# cm3-adaptor-board.net
KiCad netlist of a schematic drawn in EAGLE
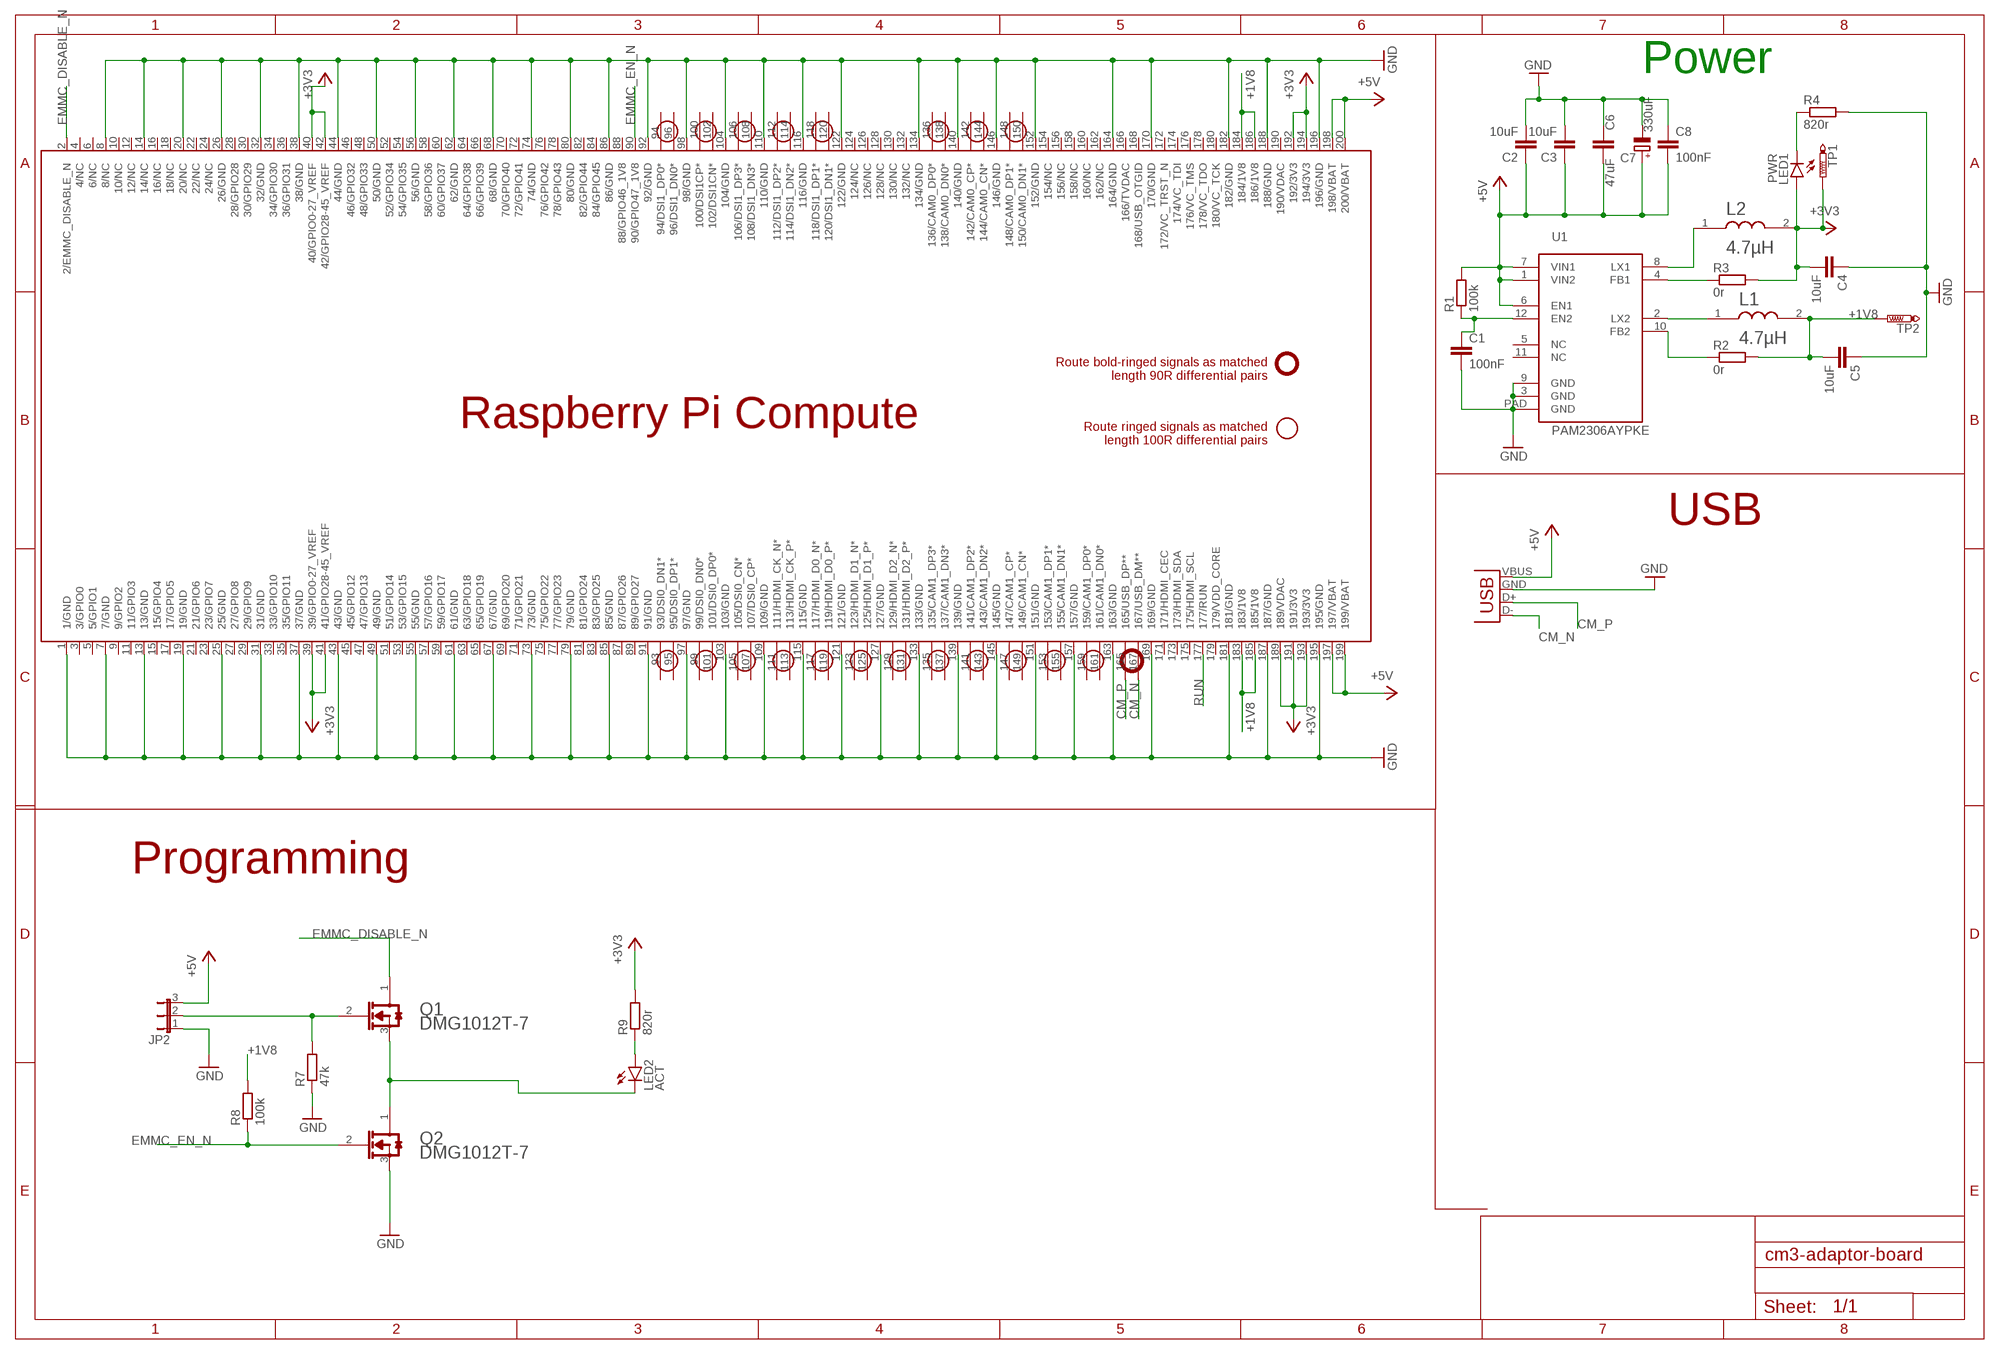
[diagram p0: schematic, sheet 1]

(export (version "E")
  (design (tool "Eeschema 10.0.6"))
  (components
    (comp (ref "C1")
      (value "100nF")
      (footprint "eagle-import:C0603")
      (libsource (lib "eagle-import") (part "C-EUC0603"))
    )
    (comp (ref "C2")
      (value "10uF")
      (footprint "eagle-import:C0805")
      (libsource (lib "eagle-import") (part "C-EUC0805"))
    )
    (comp (ref "C3")
      (value "10uF")
      (footprint "eagle-import:C0805")
      (libsource (lib "eagle-import") (part "C-EUC0805"))
    )
    (comp (ref "C4")
      (value "10uF")
      (footprint "eagle-import:C0805")
      (libsource (lib "eagle-import") (part "C-EUC0805"))
    )
    (comp (ref "C5")
      (value "10uF")
      (footprint "eagle-import:C0805")
      (libsource (lib "eagle-import") (part "C-EUC0805"))
    )
    (comp (ref "C6")
      (value "47uF")
      (footprint "eagle-import:C1206")
      (libsource (lib "eagle-import") (part "C-EUC1206"))
    )
    (comp (ref "C7")
      (value "330uF")
      (footprint "eagle-import:PANASONIC_D")
      (libsource (lib "eagle-import") (part "CPOL-EUD"))
    )
    (comp (ref "C8")
      (value "100nF")
      (footprint "eagle-import:C0603")
      (libsource (lib "eagle-import") (part "C-EUC0603"))
    )
    (comp (ref "JP1")
      (value "USB-A-H")
      (footprint "eagle-import:USB-A-H")
      (libsource (lib "eagle-import") (part "USB-A-H"))
    )
    (comp (ref "JP2")
      (value "JP2E")
      (footprint "eagle-import:JP2")
      (libsource (lib "eagle-import") (part "JP2E"))
    )
    (comp (ref "L1")
      (value "BOURNS_SRN4018-4R7MBOURNS_SRN4018-4R7M_0_0")
      (footprint "eagle-import:BOURNS_SRN4018-4R7M_0")
      (fields
        (field (name "DIGIKEY_PART_NUMBER") "SRN4018-4R7MCT-ND")
        (field (name "MF") "Bourns")
        (field (name "MOUSER_PART_NUMBER") "652-SRN4018-4R7M")
      )
      (libsource (lib "eagle-import") (part "BOURNS_SRN4018-4R7MBOURNS_SRN4018-4R7M_0_0"))
    )
    (comp (ref "L2")
      (value "BOURNS_SRN4018-4R7MBOURNS_SRN4018-4R7M_0_0")
      (footprint "eagle-import:BOURNS_SRN4018-4R7M_0")
      (fields
        (field (name "DIGIKEY_PART_NUMBER") "SRN4018-4R7MCT-ND")
        (field (name "MF") "Bourns")
        (field (name "MOUSER_PART_NUMBER") "652-SRN4018-4R7M")
      )
      (libsource (lib "eagle-import") (part "BOURNS_SRN4018-4R7MBOURNS_SRN4018-4R7M_0_0"))
    )
    (comp (ref "LED1")
      (value "PWR")
      (footprint "eagle-import:CHIP-LED0603")
      (libsource (lib "eagle-import") (part "LEDCHIP-LED0603"))
    )
    (comp (ref "LED2")
      (value "ACT")
      (footprint "eagle-import:CHIP-LED0603")
      (libsource (lib "eagle-import") (part "LEDCHIP-LED0603"))
    )
    (comp (ref "PCB1")
      (value "RPI_COMPUTE")
      (footprint "eagle-import:RPI_COMPUTE")
      (libsource (lib "eagle-import") (part "RPI_COMPUTE"))
    )
    (comp (ref "Q1")
      (value "DIODES_DMG1012T-7DIODES_DMG1012T-7_0_0")
      (footprint "eagle-import:DIODES_DMG1012T-7_0")
      (fields
        (field (name "DIGIKEY_PART_NUMBER") "DMG1012T-7DICT-ND")
        (field (name "MF") "Diodes")
        (field (name "MOUSER_PART_NUMBER") "621-DMG1012T-7")
      )
      (libsource (lib "eagle-import") (part "DIODES_DMG1012T-7DIODES_DMG1012T-7_0_0"))
    )
    (comp (ref "Q2")
      (value "DIODES_DMG1012T-7DIODES_DMG1012T-7_0_0")
      (footprint "eagle-import:DIODES_DMG1012T-7_0")
      (fields
        (field (name "DIGIKEY_PART_NUMBER") "DMG1012T-7DICT-ND")
        (field (name "MF") "Diodes")
        (field (name "MOUSER_PART_NUMBER") "621-DMG1012T-7")
      )
      (libsource (lib "eagle-import") (part "DIODES_DMG1012T-7DIODES_DMG1012T-7_0_0"))
    )
    (comp (ref "R1")
      (value "100k")
      (footprint "eagle-import:R0603")
      (libsource (lib "eagle-import") (part "R-EU_R0603"))
    )
    (comp (ref "R2")
      (value "0r")
      (footprint "eagle-import:R0603")
      (libsource (lib "eagle-import") (part "R-EU_R0603"))
    )
    (comp (ref "R3")
      (value "0r")
      (footprint "eagle-import:R0603")
      (libsource (lib "eagle-import") (part "R-EU_R0603"))
    )
    (comp (ref "R4")
      (value "820r")
      (footprint "eagle-import:R0603")
      (libsource (lib "eagle-import") (part "R-EU_R0603"))
    )
    (comp (ref "R7")
      (value "47k")
      (footprint "eagle-import:R0603")
      (libsource (lib "eagle-import") (part "R-EU_R0603"))
    )
    (comp (ref "R8")
      (value "100k")
      (footprint "eagle-import:R0603")
      (libsource (lib "eagle-import") (part "R-EU_R0603"))
    )
    (comp (ref "R9")
      (value "820r")
      (footprint "eagle-import:R0603")
      (libsource (lib "eagle-import") (part "R-EU_R0603"))
    )
    (comp (ref "TP1")
      (value "PTR1B1,27")
      (footprint "eagle-import:B1,27")
      (libsource (lib "eagle-import") (part "PTR1B1,27"))
    )
    (comp (ref "TP2")
      (value "PTR1B1,27")
      (footprint "eagle-import:B1,27")
      (libsource (lib "eagle-import") (part "PTR1B1,27"))
    )
    (comp (ref "U1")
      (value "PAM2306AYPKE")
      (footprint "eagle-import:WDFN-12L")
      (libsource (lib "eagle-import") (part "PAM2306AYPKE"))
    )
  )
  (nets
    (net (code "1") (name "+3V3") (class "Default")
      (node (ref "C4") (pin "2") (pinfunction "2_2") (pintype "passive"))
      (node (ref "L2") (pin "2") (pinfunction "2_2") (pintype "bidirectional"))
      (node (ref "LED1") (pin "A") (pinfunction "A_A") (pintype "passive"))
      (node (ref "PCB1") (pin "189") (pinfunction "189/VDAC_189") (pintype "bidirectional"))
      (node (ref "PCB1") (pin "191") (pinfunction "191/3V3_191") (pintype "bidirectional"))
      (node (ref "PCB1") (pin "192") (pinfunction "192/3V3_192") (pintype "bidirectional"))
      (node (ref "PCB1") (pin "193") (pinfunction "193/3V3_193") (pintype "bidirectional"))
      (node (ref "PCB1") (pin "194") (pinfunction "194/3V3_194") (pintype "bidirectional"))
      (node (ref "PCB1") (pin "39") (pinfunction "39/GPIO0-27_VREF_39") (pintype "bidirectional"))
      (node (ref "PCB1") (pin "40") (pinfunction "40/GPIO0-27_VREF_40") (pintype "bidirectional"))
      (node (ref "PCB1") (pin "41") (pinfunction "41/GPIO28-45_VREF_41") (pintype "bidirectional"))
      (node (ref "PCB1") (pin "42") (pinfunction "42/GPIO28-45_VREF_42") (pintype "bidirectional"))
      (node (ref "R3") (pin "2") (pinfunction "2_2") (pintype "passive"))
      (node (ref "R9") (pin "2") (pinfunction "2_2") (pintype "passive"))
      (node (ref "TP1") (pin "TP") (pinfunction "TP_TP") (pintype "input"))
    )
    (net (code "2") (name "+5V") (class "Default")
      (node (ref "C2") (pin "1") (pinfunction "1_1") (pintype "passive"))
      (node (ref "C3") (pin "1") (pinfunction "1_1") (pintype "passive"))
      (node (ref "C6") (pin "2") (pinfunction "2_2") (pintype "passive"))
      (node (ref "C7") (pin "+") (pinfunction "+_+") (pintype "passive"))
      (node (ref "C8") (pin "2") (pinfunction "2_2") (pintype "passive"))
      (node (ref "JP1") (pin "VBUS") (pinfunction "GND_VBUS") (pintype "bidirectional"))
      (node (ref "JP2") (pin "3") (pinfunction "3_3") (pintype "passive"))
      (node (ref "PCB1") (pin "197") (pinfunction "197/VBAT_197") (pintype "bidirectional"))
      (node (ref "PCB1") (pin "198") (pinfunction "198/VBAT_198") (pintype "bidirectional"))
      (node (ref "PCB1") (pin "199") (pinfunction "199/VBAT_199") (pintype "bidirectional"))
      (node (ref "PCB1") (pin "200") (pinfunction "200/VBAT_200") (pintype "bidirectional"))
      (node (ref "R1") (pin "2") (pinfunction "2_2") (pintype "passive"))
      (node (ref "U1") (pin "1") (pinfunction "VIN2_1") (pintype "power_in"))
      (node (ref "U1") (pin "6") (pinfunction "EN1_6") (pintype "input"))
      (node (ref "U1") (pin "7") (pinfunction "VIN1_7") (pintype "power_in"))
    )
    (net (code "3") (name "/+1V8") (class "Default")
      (node (ref "C5") (pin "2") (pinfunction "2_2") (pintype "passive"))
      (node (ref "L1") (pin "2") (pinfunction "2_2") (pintype "bidirectional"))
      (node (ref "PCB1") (pin "183") (pinfunction "183/1V8_183") (pintype "bidirectional"))
      (node (ref "PCB1") (pin "184") (pinfunction "184/1V8_184") (pintype "bidirectional"))
      (node (ref "PCB1") (pin "185") (pinfunction "185/1V8_185") (pintype "bidirectional"))
      (node (ref "PCB1") (pin "186") (pinfunction "186/1V8_186") (pintype "bidirectional"))
      (node (ref "R2") (pin "2") (pinfunction "2_2") (pintype "passive"))
      (node (ref "R8") (pin "2") (pinfunction "2_2") (pintype "passive"))
      (node (ref "TP2") (pin "TP") (pinfunction "TP_TP") (pintype "input"))
    )
    (net (code "4") (name "/CM_N") (class "Default")
      (node (ref "JP1") (pin "D-") (pinfunction "D+_D-") (pintype "bidirectional"))
      (node (ref "PCB1") (pin "167") (pinfunction "167/USB_DM**_167") (pintype "bidirectional"))
    )
    (net (code "5") (name "/CM_P") (class "Default")
      (node (ref "JP1") (pin "D+") (pinfunction "D-_D+") (pintype "bidirectional"))
      (node (ref "PCB1") (pin "165") (pinfunction "165/USB_DP**_165") (pintype "bidirectional"))
    )
    (net (code "6") (name "/EMMC_DISABLE_N") (class "Default")
      (node (ref "PCB1") (pin "2") (pinfunction "2/EMMC_DISABLE_N_2") (pintype "bidirectional"))
      (node (ref "Q1") (pin "1") (pinfunction "DRAIN_1") (pintype "bidirectional"))
    )
    (net (code "7") (name "/EMMC_EN_N") (class "Default")
      (node (ref "PCB1") (pin "90") (pinfunction "90/GPIO47_1V8_90") (pintype "bidirectional"))
      (node (ref "Q2") (pin "2") (pinfunction "GATE_2") (pintype "bidirectional"))
      (node (ref "R8") (pin "1") (pinfunction "1_1") (pintype "passive"))
    )
    (net (code "8") (name "/RUN") (class "Default")
      (node (ref "PCB1") (pin "177") (pinfunction "177/RUN_177") (pintype "bidirectional"))
    )
    (net (code "9") (name "GND") (class "Default")
      (node (ref "C1") (pin "2") (pinfunction "2_2") (pintype "passive"))
      (node (ref "C2") (pin "2") (pinfunction "2_2") (pintype "passive"))
      (node (ref "C3") (pin "2") (pinfunction "2_2") (pintype "passive"))
      (node (ref "C4") (pin "1") (pinfunction "1_1") (pintype "passive"))
      (node (ref "C5") (pin "1") (pinfunction "1_1") (pintype "passive"))
      (node (ref "C6") (pin "1") (pinfunction "1_1") (pintype "passive"))
      (node (ref "C7") (pin "-") (pinfunction "-_-") (pintype "passive"))
      (node (ref "C8") (pin "1") (pinfunction "1_1") (pintype "passive"))
      (node (ref "JP1") (pin "GND") (pinfunction "VBUS_GND") (pintype "bidirectional"))
      (node (ref "JP2") (pin "1") (pinfunction "1_1") (pintype "passive"))
      (node (ref "PCB1") (pin "1") (pinfunction "1/GND_1") (pintype "bidirectional"))
      (node (ref "PCB1") (pin "103") (pinfunction "103/GND_103") (pintype "bidirectional"))
      (node (ref "PCB1") (pin "104") (pinfunction "104/GND_104") (pintype "bidirectional"))
      (node (ref "PCB1") (pin "109") (pinfunction "109/GND_109") (pintype "bidirectional"))
      (node (ref "PCB1") (pin "110") (pinfunction "110/GND_110") (pintype "bidirectional"))
      (node (ref "PCB1") (pin "115") (pinfunction "115/GND_115") (pintype "bidirectional"))
      (node (ref "PCB1") (pin "116") (pinfunction "116/GND_116") (pintype "bidirectional"))
      (node (ref "PCB1") (pin "121") (pinfunction "121/GND_121") (pintype "bidirectional"))
      (node (ref "PCB1") (pin "122") (pinfunction "122/GND_122") (pintype "bidirectional"))
      (node (ref "PCB1") (pin "127") (pinfunction "127/GND_127") (pintype "bidirectional"))
      (node (ref "PCB1") (pin "13") (pinfunction "13/GND_13") (pintype "bidirectional"))
      (node (ref "PCB1") (pin "133") (pinfunction "133/GND_133") (pintype "bidirectional"))
      (node (ref "PCB1") (pin "134") (pinfunction "134/GND_134") (pintype "bidirectional"))
      (node (ref "PCB1") (pin "139") (pinfunction "139/GND_139") (pintype "bidirectional"))
      (node (ref "PCB1") (pin "14") (pinfunction "14/NC_14") (pintype "bidirectional"))
      (node (ref "PCB1") (pin "140") (pinfunction "140/GND_140") (pintype "bidirectional"))
      (node (ref "PCB1") (pin "145") (pinfunction "145/GND_145") (pintype "bidirectional"))
      (node (ref "PCB1") (pin "146") (pinfunction "146/GND_146") (pintype "bidirectional"))
      (node (ref "PCB1") (pin "151") (pinfunction "151/GND_151") (pintype "bidirectional"))
      (node (ref "PCB1") (pin "152") (pinfunction "152/GND_152") (pintype "bidirectional"))
      (node (ref "PCB1") (pin "157") (pinfunction "157/GND_157") (pintype "bidirectional"))
      (node (ref "PCB1") (pin "163") (pinfunction "163/GND_163") (pintype "bidirectional"))
      (node (ref "PCB1") (pin "164") (pinfunction "164/GND_164") (pintype "bidirectional"))
      (node (ref "PCB1") (pin "169") (pinfunction "169/GND_169") (pintype "bidirectional"))
      (node (ref "PCB1") (pin "170") (pinfunction "170/GND_170") (pintype "bidirectional"))
      (node (ref "PCB1") (pin "181") (pinfunction "181/GND_181") (pintype "bidirectional"))
      (node (ref "PCB1") (pin "182") (pinfunction "182/GND_182") (pintype "bidirectional"))
      (node (ref "PCB1") (pin "187") (pinfunction "187/GND_187") (pintype "bidirectional"))
      (node (ref "PCB1") (pin "188") (pinfunction "188/GND_188") (pintype "bidirectional"))
      (node (ref "PCB1") (pin "19") (pinfunction "19/GND_19") (pintype "bidirectional"))
      (node (ref "PCB1") (pin "195") (pinfunction "195/GND_195") (pintype "bidirectional"))
      (node (ref "PCB1") (pin "196") (pinfunction "196/GND_196") (pintype "bidirectional"))
      (node (ref "PCB1") (pin "20") (pinfunction "20/NC_20") (pintype "bidirectional"))
      (node (ref "PCB1") (pin "25") (pinfunction "25/GND_25") (pintype "bidirectional"))
      (node (ref "PCB1") (pin "26") (pinfunction "26/GND_26") (pintype "bidirectional"))
      (node (ref "PCB1") (pin "31") (pinfunction "31/GND_31") (pintype "bidirectional"))
      (node (ref "PCB1") (pin "32") (pinfunction "32/GND_32") (pintype "bidirectional"))
      (node (ref "PCB1") (pin "37") (pinfunction "37/GND_37") (pintype "bidirectional"))
      (node (ref "PCB1") (pin "38") (pinfunction "38/GND_38") (pintype "bidirectional"))
      (node (ref "PCB1") (pin "43") (pinfunction "43/GND_43") (pintype "bidirectional"))
      (node (ref "PCB1") (pin "44") (pinfunction "44/GND_44") (pintype "bidirectional"))
      (node (ref "PCB1") (pin "49") (pinfunction "49/GND_49") (pintype "bidirectional"))
      (node (ref "PCB1") (pin "50") (pinfunction "50/GND_50") (pintype "bidirectional"))
      (node (ref "PCB1") (pin "55") (pinfunction "55/GND_55") (pintype "bidirectional"))
      (node (ref "PCB1") (pin "56") (pinfunction "56/GND_56") (pintype "bidirectional"))
      (node (ref "PCB1") (pin "61") (pinfunction "61/GND_61") (pintype "bidirectional"))
      (node (ref "PCB1") (pin "62") (pinfunction "62/GND_62") (pintype "bidirectional"))
      (node (ref "PCB1") (pin "67") (pinfunction "67/GND_67") (pintype "bidirectional"))
      (node (ref "PCB1") (pin "68") (pinfunction "68/GND_68") (pintype "bidirectional"))
      (node (ref "PCB1") (pin "7") (pinfunction "7/GND_7") (pintype "bidirectional"))
      (node (ref "PCB1") (pin "73") (pinfunction "73/GND_73") (pintype "bidirectional"))
      (node (ref "PCB1") (pin "74") (pinfunction "74/GND_74") (pintype "bidirectional"))
      (node (ref "PCB1") (pin "79") (pinfunction "79/GND_79") (pintype "bidirectional"))
      (node (ref "PCB1") (pin "8") (pinfunction "8/NC_8") (pintype "bidirectional"))
      (node (ref "PCB1") (pin "80") (pinfunction "80/GND_80") (pintype "bidirectional"))
      (node (ref "PCB1") (pin "85") (pinfunction "85/GND_85") (pintype "bidirectional"))
      (node (ref "PCB1") (pin "86") (pinfunction "86/GND_86") (pintype "bidirectional"))
      (node (ref "PCB1") (pin "91") (pinfunction "91/GND_91") (pintype "bidirectional"))
      (node (ref "PCB1") (pin "92") (pinfunction "92/GND_92") (pintype "bidirectional"))
      (node (ref "PCB1") (pin "97") (pinfunction "97/GND_97") (pintype "bidirectional"))
      (node (ref "PCB1") (pin "98") (pinfunction "98/GND_98") (pintype "bidirectional"))
      (node (ref "Q2") (pin "3") (pinfunction "SOURCE_3") (pintype "bidirectional"))
      (node (ref "R4") (pin "2") (pinfunction "2_2") (pintype "passive"))
      (node (ref "R7") (pin "1") (pinfunction "1_1") (pintype "passive"))
      (node (ref "U1") (pin "3") (pinfunction "GND_3") (pintype "power_in"))
      (node (ref "U1") (pin "9") (pinfunction "GND_9") (pintype "power_in"))
      (node (ref "U1") (pin "PAD") (pinfunction "GND_PAD") (pintype "power_in"))
    )
    (net (code "10") (name "Net-(LED1-PadC)") (class "Default")
      (node (ref "LED1") (pin "C") (pinfunction "C_C") (pintype "passive"))
      (node (ref "R4") (pin "1") (pinfunction "1_1") (pintype "passive"))
    )
    (net (code "11") (name "Net-(LED2-PadA)") (class "Default")
      (node (ref "LED2") (pin "A") (pinfunction "A_A") (pintype "passive"))
      (node (ref "R9") (pin "1") (pinfunction "1_1") (pintype "passive"))
    )
    (net (code "12") (name "Net-(Q1-GATE)") (class "Default")
      (node (ref "JP2") (pin "2") (pinfunction "2_2") (pintype "passive"))
      (node (ref "Q1") (pin "2") (pinfunction "GATE_2") (pintype "bidirectional"))
      (node (ref "R7") (pin "2") (pinfunction "2_2") (pintype "passive"))
    )
    (net (code "13") (name "Net-(Q1-SOURCE)") (class "Default")
      (node (ref "LED2") (pin "C") (pinfunction "C_C") (pintype "passive"))
      (node (ref "Q1") (pin "3") (pinfunction "SOURCE_3") (pintype "bidirectional"))
      (node (ref "Q2") (pin "1") (pinfunction "DRAIN_1") (pintype "bidirectional"))
    )
    (net (code "14") (name "Net-(U1-EN2)") (class "Default")
      (node (ref "C1") (pin "1") (pinfunction "1_1") (pintype "passive"))
      (node (ref "R1") (pin "1") (pinfunction "1_1") (pintype "passive"))
      (node (ref "U1") (pin "12") (pinfunction "EN2_12") (pintype "input"))
    )
    (net (code "15") (name "Net-(U1-FB1)") (class "Default")
      (node (ref "R3") (pin "1") (pinfunction "1_1") (pintype "passive"))
      (node (ref "U1") (pin "4") (pinfunction "FB1_4") (pintype "input"))
    )
    (net (code "16") (name "Net-(U1-FB2)") (class "Default")
      (node (ref "R2") (pin "1") (pinfunction "1_1") (pintype "passive"))
      (node (ref "U1") (pin "10") (pinfunction "FB2_10") (pintype "input"))
    )
    (net (code "17") (name "Net-(U1-LX1)") (class "Default")
      (node (ref "L2") (pin "1") (pinfunction "1_1") (pintype "bidirectional"))
      (node (ref "U1") (pin "8") (pinfunction "LX1_8") (pintype "power_in"))
    )
    (net (code "18") (name "Net-(U1-LX2)") (class "Default")
      (node (ref "L1") (pin "1") (pinfunction "1_1") (pintype "bidirectional"))
      (node (ref "U1") (pin "2") (pinfunction "LX2_2") (pintype "power_in"))
    )
    (net (code "19") (name "unconnected-(PCB1-3{slash}GPIO0-Pad3)") (class "Default")
      (node (ref "PCB1") (pin "3") (pinfunction "3/GPIO0_3") (pintype "bidirectional"))
    )
    (net (code "20") (name "unconnected-(PCB1-4{slash}NC-Pad4)") (class "Default")
      (node (ref "PCB1") (pin "4") (pinfunction "4/NC_4") (pintype "bidirectional"))
    )
    (net (code "21") (name "unconnected-(PCB1-5{slash}GPIO1-Pad5)") (class "Default")
      (node (ref "PCB1") (pin "5") (pinfunction "5/GPIO1_5") (pintype "bidirectional"))
    )
    (net (code "22") (name "unconnected-(PCB1-6{slash}NC-Pad6)") (class "Default")
      (node (ref "PCB1") (pin "6") (pinfunction "6/NC_6") (pintype "bidirectional"))
    )
    (net (code "23") (name "unconnected-(PCB1-9{slash}GPIO2-Pad9)") (class "Default")
      (node (ref "PCB1") (pin "9") (pinfunction "9/GPIO2_9") (pintype "bidirectional"))
    )
    (net (code "24") (name "unconnected-(PCB1-10{slash}NC-Pad10)") (class "Default")
      (node (ref "PCB1") (pin "10") (pinfunction "10/NC_10") (pintype "bidirectional"))
    )
    (net (code "25") (name "unconnected-(PCB1-11{slash}GPIO3-Pad11)") (class "Default")
      (node (ref "PCB1") (pin "11") (pinfunction "11/GPIO3_11") (pintype "bidirectional"))
    )
    (net (code "26") (name "unconnected-(PCB1-12{slash}NC-Pad12)") (class "Default")
      (node (ref "PCB1") (pin "12") (pinfunction "12/NC_12") (pintype "bidirectional"))
    )
    (net (code "27") (name "unconnected-(PCB1-15{slash}GPIO4-Pad15)") (class "Default")
      (node (ref "PCB1") (pin "15") (pinfunction "15/GPIO4_15") (pintype "bidirectional"))
    )
    (net (code "28") (name "unconnected-(PCB1-16{slash}NC-Pad16)") (class "Default")
      (node (ref "PCB1") (pin "16") (pinfunction "16/NC_16") (pintype "bidirectional"))
    )
    (net (code "29") (name "unconnected-(PCB1-17{slash}GPIO5-Pad17)") (class "Default")
      (node (ref "PCB1") (pin "17") (pinfunction "17/GPIO5_17") (pintype "bidirectional"))
    )
    (net (code "30") (name "unconnected-(PCB1-18{slash}NC-Pad18)") (class "Default")
      (node (ref "PCB1") (pin "18") (pinfunction "18/NC_18") (pintype "bidirectional"))
    )
    (net (code "31") (name "unconnected-(PCB1-21{slash}GPIO6-Pad21)") (class "Default")
      (node (ref "PCB1") (pin "21") (pinfunction "21/GPIO6_21") (pintype "bidirectional"))
    )
    (net (code "32") (name "unconnected-(PCB1-22{slash}NC-Pad22)") (class "Default")
      (node (ref "PCB1") (pin "22") (pinfunction "22/NC_22") (pintype "bidirectional"))
    )
    (net (code "33") (name "unconnected-(PCB1-23{slash}GPIO7-Pad23)") (class "Default")
      (node (ref "PCB1") (pin "23") (pinfunction "23/GPIO7_23") (pintype "bidirectional"))
    )
    (net (code "34") (name "unconnected-(PCB1-24{slash}NC-Pad24)") (class "Default")
      (node (ref "PCB1") (pin "24") (pinfunction "24/NC_24") (pintype "bidirectional"))
    )
    (net (code "35") (name "unconnected-(PCB1-27{slash}GPIO8-Pad27)") (class "Default")
      (node (ref "PCB1") (pin "27") (pinfunction "27/GPIO8_27") (pintype "bidirectional"))
    )
    (net (code "36") (name "unconnected-(PCB1-28{slash}GPIO28-Pad28)") (class "Default")
      (node (ref "PCB1") (pin "28") (pinfunction "28/GPIO28_28") (pintype "bidirectional"))
    )
    (net (code "37") (name "unconnected-(PCB1-29{slash}GPIO9-Pad29)") (class "Default")
      (node (ref "PCB1") (pin "29") (pinfunction "29/GPIO9_29") (pintype "bidirectional"))
    )
    (net (code "38") (name "unconnected-(PCB1-30{slash}GPIO29-Pad30)") (class "Default")
      (node (ref "PCB1") (pin "30") (pinfunction "30/GPIO29_30") (pintype "bidirectional"))
    )
    (net (code "39") (name "unconnected-(PCB1-33{slash}GPIO10-Pad33)") (class "Default")
      (node (ref "PCB1") (pin "33") (pinfunction "33/GPIO10_33") (pintype "bidirectional"))
    )
    (net (code "40") (name "unconnected-(PCB1-34{slash}GPIO30-Pad34)") (class "Default")
      (node (ref "PCB1") (pin "34") (pinfunction "34/GPIO30_34") (pintype "bidirectional"))
    )
    (net (code "41") (name "unconnected-(PCB1-35{slash}GPIO11-Pad35)") (class "Default")
      (node (ref "PCB1") (pin "35") (pinfunction "35/GPIO11_35") (pintype "bidirectional"))
    )
    (net (code "42") (name "unconnected-(PCB1-36{slash}GPIO31-Pad36)") (class "Default")
      (node (ref "PCB1") (pin "36") (pinfunction "36/GPIO31_36") (pintype "bidirectional"))
    )
    (net (code "43") (name "unconnected-(PCB1-45{slash}GPIO12-Pad45)") (class "Default")
      (node (ref "PCB1") (pin "45") (pinfunction "45/GPIO12_45") (pintype "bidirectional"))
    )
    (net (code "44") (name "unconnected-(PCB1-46{slash}GPIO32-Pad46)") (class "Default")
      (node (ref "PCB1") (pin "46") (pinfunction "46/GPIO32_46") (pintype "bidirectional"))
    )
    (net (code "45") (name "unconnected-(PCB1-47{slash}GPIO13-Pad47)") (class "Default")
      (node (ref "PCB1") (pin "47") (pinfunction "47/GPIO13_47") (pintype "bidirectional"))
    )
    (net (code "46") (name "unconnected-(PCB1-48{slash}GPIO33-Pad48)") (class "Default")
      (node (ref "PCB1") (pin "48") (pinfunction "48/GPIO33_48") (pintype "bidirectional"))
    )
    (net (code "47") (name "unconnected-(PCB1-51{slash}GPIO14-Pad51)") (class "Default")
      (node (ref "PCB1") (pin "51") (pinfunction "51/GPIO14_51") (pintype "bidirectional"))
    )
    (net (code "48") (name "unconnected-(PCB1-52{slash}GPIO34-Pad52)") (class "Default")
      (node (ref "PCB1") (pin "52") (pinfunction "52/GPIO34_52") (pintype "bidirectional"))
    )
    (net (code "49") (name "unconnected-(PCB1-53{slash}GPIO15-Pad53)") (class "Default")
      (node (ref "PCB1") (pin "53") (pinfunction "53/GPIO15_53") (pintype "bidirectional"))
    )
    (net (code "50") (name "unconnected-(PCB1-54{slash}GPIO35-Pad54)") (class "Default")
      (node (ref "PCB1") (pin "54") (pinfunction "54/GPIO35_54") (pintype "bidirectional"))
    )
    (net (code "51") (name "unconnected-(PCB1-57{slash}GPIO16-Pad57)") (class "Default")
      (node (ref "PCB1") (pin "57") (pinfunction "57/GPIO16_57") (pintype "bidirectional"))
    )
    (net (code "52") (name "unconnected-(PCB1-58{slash}GPIO36-Pad58)") (class "Default")
      (node (ref "PCB1") (pin "58") (pinfunction "58/GPIO36_58") (pintype "bidirectional"))
    )
    (net (code "53") (name "unconnected-(PCB1-59{slash}GPIO17-Pad59)") (class "Default")
      (node (ref "PCB1") (pin "59") (pinfunction "59/GPIO17_59") (pintype "bidirectional"))
    )
    (net (code "54") (name "unconnected-(PCB1-60{slash}GPIO37-Pad60)") (class "Default")
      (node (ref "PCB1") (pin "60") (pinfunction "60/GPIO37_60") (pintype "bidirectional"))
    )
    (net (code "55") (name "unconnected-(PCB1-63{slash}GPIO18-Pad63)") (class "Default")
      (node (ref "PCB1") (pin "63") (pinfunction "63/GPIO18_63") (pintype "bidirectional"))
    )
    (net (code "56") (name "unconnected-(PCB1-64{slash}GPIO38-Pad64)") (class "Default")
      (node (ref "PCB1") (pin "64") (pinfunction "64/GPIO38_64") (pintype "bidirectional"))
    )
    (net (code "57") (name "unconnected-(PCB1-65{slash}GPIO19-Pad65)") (class "Default")
      (node (ref "PCB1") (pin "65") (pinfunction "65/GPIO19_65") (pintype "bidirectional"))
    )
    (net (code "58") (name "unconnected-(PCB1-66{slash}GPIO39-Pad66)") (class "Default")
      (node (ref "PCB1") (pin "66") (pinfunction "66/GPIO39_66") (pintype "bidirectional"))
    )
    (net (code "59") (name "unconnected-(PCB1-69{slash}GPIO20-Pad69)") (class "Default")
      (node (ref "PCB1") (pin "69") (pinfunction "69/GPIO20_69") (pintype "bidirectional"))
    )
    (net (code "60") (name "unconnected-(PCB1-70{slash}GPIO40-Pad70)") (class "Default")
      (node (ref "PCB1") (pin "70") (pinfunction "70/GPIO40_70") (pintype "bidirectional"))
    )
    (net (code "61") (name "unconnected-(PCB1-71{slash}GPIO21-Pad71)") (class "Default")
      (node (ref "PCB1") (pin "71") (pinfunction "71/GPIO21_71") (pintype "bidirectional"))
    )
    (net (code "62") (name "unconnected-(PCB1-72{slash}GPIO41-Pad72)") (class "Default")
      (node (ref "PCB1") (pin "72") (pinfunction "72/GPIO41_72") (pintype "bidirectional"))
    )
    (net (code "63") (name "unconnected-(PCB1-75{slash}GPIO22-Pad75)") (class "Default")
      (node (ref "PCB1") (pin "75") (pinfunction "75/GPIO22_75") (pintype "bidirectional"))
    )
    (net (code "64") (name "unconnected-(PCB1-76{slash}GPIO42-Pad76)") (class "Default")
      (node (ref "PCB1") (pin "76") (pinfunction "76/GPIO42_76") (pintype "bidirectional"))
    )
    (net (code "65") (name "unconnected-(PCB1-77{slash}GPIO23-Pad77)") (class "Default")
      (node (ref "PCB1") (pin "77") (pinfunction "77/GPIO23_77") (pintype "bidirectional"))
    )
    (net (code "66") (name "unconnected-(PCB1-78{slash}GPIO43-Pad78)") (class "Default")
      (node (ref "PCB1") (pin "78") (pinfunction "78/GPIO43_78") (pintype "bidirectional"))
    )
    (net (code "67") (name "unconnected-(PCB1-81{slash}GPIO24-Pad81)") (class "Default")
      (node (ref "PCB1") (pin "81") (pinfunction "81/GPIO24_81") (pintype "bidirectional"))
    )
    (net (code "68") (name "unconnected-(PCB1-82{slash}GPIO44-Pad82)") (class "Default")
      (node (ref "PCB1") (pin "82") (pinfunction "82/GPIO44_82") (pintype "bidirectional"))
    )
    (net (code "69") (name "unconnected-(PCB1-83{slash}GPIO25-Pad83)") (class "Default")
      (node (ref "PCB1") (pin "83") (pinfunction "83/GPIO25_83") (pintype "bidirectional"))
    )
    (net (code "70") (name "unconnected-(PCB1-84{slash}GPIO45-Pad84)") (class "Default")
      (node (ref "PCB1") (pin "84") (pinfunction "84/GPIO45_84") (pintype "bidirectional"))
    )
    (net (code "71") (name "unconnected-(PCB1-87{slash}GPIO26-Pad87)") (class "Default")
      (node (ref "PCB1") (pin "87") (pinfunction "87/GPIO26_87") (pintype "bidirectional"))
    )
    (net (code "72") (name "unconnected-(PCB1-88{slash}GPIO46_1V8-Pad88)") (class "Default")
      (node (ref "PCB1") (pin "88") (pinfunction "88/GPIO46_1V8_88") (pintype "bidirectional"))
    )
    (net (code "73") (name "unconnected-(PCB1-89{slash}GPIO27-Pad89)") (class "Default")
      (node (ref "PCB1") (pin "89") (pinfunction "89/GPIO27_89") (pintype "bidirectional"))
    )
    (net (code "74") (name "unconnected-(PCB1-93{slash}DSI0_DN1*-Pad93)") (class "Default")
      (node (ref "PCB1") (pin "93") (pinfunction "93/DSI0_DN1*_93") (pintype "bidirectional"))
    )
    (net (code "75") (name "unconnected-(PCB1-94{slash}DSI1_DP0*-Pad94)") (class "Default")
      (node (ref "PCB1") (pin "94") (pinfunction "94/DSI1_DP0*_94") (pintype "bidirectional"))
    )
    (net (code "76") (name "unconnected-(PCB1-95{slash}DSI0_DP1*-Pad95)") (class "Default")
      (node (ref "PCB1") (pin "95") (pinfunction "95/DSI0_DP1*_95") (pintype "bidirectional"))
    )
    (net (code "77") (name "unconnected-(PCB1-96{slash}DSI1_DN0*-Pad96)") (class "Default")
      (node (ref "PCB1") (pin "96") (pinfunction "96/DSI1_DN0*_96") (pintype "bidirectional"))
    )
    (net (code "78") (name "unconnected-(PCB1-99{slash}DSI0_DN0*-Pad99)") (class "Default")
      (node (ref "PCB1") (pin "99") (pinfunction "99/DSI0_DN0*_99") (pintype "bidirectional"))
    )
    (net (code "79") (name "unconnected-(PCB1-100{slash}DSI1CP*-Pad100)") (class "Default")
      (node (ref "PCB1") (pin "100") (pinfunction "100/DSI1CP*_100") (pintype "bidirectional"))
    )
    (net (code "80") (name "unconnected-(PCB1-101{slash}DSI0_DP0*-Pad101)") (class "Default")
      (node (ref "PCB1") (pin "101") (pinfunction "101/DSI0_DP0*_101") (pintype "bidirectional"))
    )
    (net (code "81") (name "unconnected-(PCB1-102{slash}DSI1CN*-Pad102)") (class "Default")
      (node (ref "PCB1") (pin "102") (pinfunction "102/DSI1CN*_102") (pintype "bidirectional"))
    )
    (net (code "82") (name "unconnected-(PCB1-105{slash}DSI0_CN*-Pad105)") (class "Default")
      (node (ref "PCB1") (pin "105") (pinfunction "105/DSI0_CN*_105") (pintype "bidirectional"))
    )
    (net (code "83") (name "unconnected-(PCB1-106{slash}DSI1_DP3*-Pad106)") (class "Default")
      (node (ref "PCB1") (pin "106") (pinfunction "106/DSI1_DP3*_106") (pintype "bidirectional"))
    )
    (net (code "84") (name "unconnected-(PCB1-107{slash}DSI0_CP*-Pad107)") (class "Default")
      (node (ref "PCB1") (pin "107") (pinfunction "107/DSI0_CP*_107") (pintype "bidirectional"))
    )
    (net (code "85") (name "unconnected-(PCB1-108{slash}DSI1_DN3*-Pad108)") (class "Default")
      (node (ref "PCB1") (pin "108") (pinfunction "108/DSI1_DN3*_108") (pintype "bidirectional"))
    )
    (net (code "86") (name "unconnected-(PCB1-111{slash}HDMI_CK_N*-Pad111)") (class "Default")
      (node (ref "PCB1") (pin "111") (pinfunction "111/HDMI_CK_N*_111") (pintype "bidirectional"))
    )
    (net (code "87") (name "unconnected-(PCB1-112{slash}DSI1_DP2*-Pad112)") (class "Default")
      (node (ref "PCB1") (pin "112") (pinfunction "112/DSI1_DP2*_112") (pintype "bidirectional"))
    )
    (net (code "88") (name "unconnected-(PCB1-113{slash}HDMI_CK_P*-Pad113)") (class "Default")
      (node (ref "PCB1") (pin "113") (pinfunction "113/HDMI_CK_P*_113") (pintype "bidirectional"))
    )
    (net (code "89") (name "unconnected-(PCB1-114{slash}DSI1_DN2*-Pad114)") (class "Default")
      (node (ref "PCB1") (pin "114") (pinfunction "114/DSI1_DN2*_114") (pintype "bidirectional"))
    )
    (net (code "90") (name "unconnected-(PCB1-117{slash}HDMI_D0_N*-Pad117)") (class "Default")
      (node (ref "PCB1") (pin "117") (pinfunction "117/HDMI_D0_N*_117") (pintype "bidirectional"))
    )
    (net (code "91") (name "unconnected-(PCB1-118{slash}DSI1_DP1*-Pad118)") (class "Default")
      (node (ref "PCB1") (pin "118") (pinfunction "118/DSI1_DP1*_118") (pintype "bidirectional"))
    )
    (net (code "92") (name "unconnected-(PCB1-119{slash}HDMI_D0_P*-Pad119)") (class "Default")
      (node (ref "PCB1") (pin "119") (pinfunction "119/HDMI_D0_P*_119") (pintype "bidirectional"))
    )
    (net (code "93") (name "unconnected-(PCB1-120{slash}DSI1_DN1*-Pad120)") (class "Default")
      (node (ref "PCB1") (pin "120") (pinfunction "120/DSI1_DN1*_120") (pintype "bidirectional"))
    )
    (net (code "94") (name "unconnected-(PCB1-123{slash}HDMI_D1_N*-Pad123)") (class "Default")
      (node (ref "PCB1") (pin "123") (pinfunction "123/HDMI_D1_N*_123") (pintype "bidirectional"))
    )
    (net (code "95") (name "unconnected-(PCB1-124{slash}NC-Pad124)") (class "Default")
      (node (ref "PCB1") (pin "124") (pinfunction "124/NC_124") (pintype "bidirectional"))
    )
    (net (code "96") (name "unconnected-(PCB1-125{slash}HDMI_D1_P*-Pad125)") (class "Default")
      (node (ref "PCB1") (pin "125") (pinfunction "125/HDMI_D1_P*_125") (pintype "bidirectional"))
    )
    (net (code "97") (name "unconnected-(PCB1-126{slash}NC-Pad126)") (class "Default")
      (node (ref "PCB1") (pin "126") (pinfunction "126/NC_126") (pintype "bidirectional"))
    )
    (net (code "98") (name "unconnected-(PCB1-128{slash}NC-Pad128)") (class "Default")
      (node (ref "PCB1") (pin "128") (pinfunction "128/NC_128") (pintype "bidirectional"))
    )
    (net (code "99") (name "unconnected-(PCB1-129{slash}HDMI_D2_N*-Pad129)") (class "Default")
      (node (ref "PCB1") (pin "129") (pinfunction "129/HDMI_D2_N*_129") (pintype "bidirectional"))
    )
    (net (code "100") (name "unconnected-(PCB1-130{slash}NC-Pad130)") (class "Default")
      (node (ref "PCB1") (pin "130") (pinfunction "130/NC_130") (pintype "bidirectional"))
    )
    (net (code "101") (name "unconnected-(PCB1-131{slash}HDMI_D2_P*-Pad131)") (class "Default")
      (node (ref "PCB1") (pin "131") (pinfunction "131/HDMI_D2_P*_131") (pintype "bidirectional"))
    )
    (net (code "102") (name "unconnected-(PCB1-132{slash}NC-Pad132)") (class "Default")
      (node (ref "PCB1") (pin "132") (pinfunction "132/NC_132") (pintype "bidirectional"))
    )
    (net (code "103") (name "unconnected-(PCB1-135{slash}CAM1_DP3*-Pad135)") (class "Default")
      (node (ref "PCB1") (pin "135") (pinfunction "135/CAM1_DP3*_135") (pintype "bidirectional"))
    )
    (net (code "104") (name "unconnected-(PCB1-136{slash}CAM0_DP0*-Pad136)") (class "Default")
      (node (ref "PCB1") (pin "136") (pinfunction "136/CAM0_DP0*_136") (pintype "bidirectional"))
    )
    (net (code "105") (name "unconnected-(PCB1-137{slash}CAM1_DN3*-Pad137)") (class "Default")
      (node (ref "PCB1") (pin "137") (pinfunction "137/CAM1_DN3*_137") (pintype "bidirectional"))
    )
    (net (code "106") (name "unconnected-(PCB1-138{slash}CAM0_DN0*-Pad138)") (class "Default")
      (node (ref "PCB1") (pin "138") (pinfunction "138/CAM0_DN0*_138") (pintype "bidirectional"))
    )
    (net (code "107") (name "unconnected-(PCB1-141{slash}CAM1_DP2*-Pad141)") (class "Default")
      (node (ref "PCB1") (pin "141") (pinfunction "141/CAM1_DP2*_141") (pintype "bidirectional"))
    )
    (net (code "108") (name "unconnected-(PCB1-142{slash}CAM0_CP*-Pad142)") (class "Default")
      (node (ref "PCB1") (pin "142") (pinfunction "142/CAM0_CP*_142") (pintype "bidirectional"))
    )
    (net (code "109") (name "unconnected-(PCB1-143{slash}CAM1_DN2*-Pad143)") (class "Default")
      (node (ref "PCB1") (pin "143") (pinfunction "143/CAM1_DN2*_143") (pintype "bidirectional"))
    )
    (net (code "110") (name "unconnected-(PCB1-144{slash}CAM0_CN*-Pad144)") (class "Default")
      (node (ref "PCB1") (pin "144") (pinfunction "144/CAM0_CN*_144") (pintype "bidirectional"))
    )
    (net (code "111") (name "unconnected-(PCB1-147{slash}CAM1_CP*-Pad147)") (class "Default")
      (node (ref "PCB1") (pin "147") (pinfunction "147/CAM1_CP*_147") (pintype "bidirectional"))
    )
    (net (code "112") (name "unconnected-(PCB1-148{slash}CAM0_DP1*-Pad148)") (class "Default")
      (node (ref "PCB1") (pin "148") (pinfunction "148/CAM0_DP1*_148") (pintype "bidirectional"))
    )
    (net (code "113") (name "unconnected-(PCB1-149{slash}CAM1_CN*-Pad149)") (class "Default")
      (node (ref "PCB1") (pin "149") (pinfunction "149/CAM1_CN*_149") (pintype "bidirectional"))
    )
    (net (code "114") (name "unconnected-(PCB1-150{slash}CAM0_DN1*-Pad150)") (class "Default")
      (node (ref "PCB1") (pin "150") (pinfunction "150/CAM0_DN1*_150") (pintype "bidirectional"))
    )
    (net (code "115") (name "unconnected-(PCB1-153{slash}CAM1_DP1*-Pad153)") (class "Default")
      (node (ref "PCB1") (pin "153") (pinfunction "153/CAM1_DP1*_153") (pintype "bidirectional"))
    )
    (net (code "116") (name "unconnected-(PCB1-154{slash}NC-Pad154)") (class "Default")
      (node (ref "PCB1") (pin "154") (pinfunction "154/NC_154") (pintype "bidirectional"))
    )
    (net (code "117") (name "unconnected-(PCB1-155{slash}CAM1_DN1*-Pad155)") (class "Default")
      (node (ref "PCB1") (pin "155") (pinfunction "155/CAM1_DN1*_155") (pintype "bidirectional"))
    )
    (net (code "118") (name "unconnected-(PCB1-156{slash}NC-Pad156)") (class "Default")
      (node (ref "PCB1") (pin "156") (pinfunction "156/NC_156") (pintype "bidirectional"))
    )
    (net (code "119") (name "unconnected-(PCB1-158{slash}NC-Pad158)") (class "Default")
      (node (ref "PCB1") (pin "158") (pinfunction "158/NC_158") (pintype "bidirectional"))
    )
    (net (code "120") (name "unconnected-(PCB1-159{slash}CAM1_DP0*-Pad159)") (class "Default")
      (node (ref "PCB1") (pin "159") (pinfunction "159/CAM1_DP0*_159") (pintype "bidirectional"))
    )
    (net (code "121") (name "unconnected-(PCB1-160{slash}NC-Pad160)") (class "Default")
      (node (ref "PCB1") (pin "160") (pinfunction "160/NC_160") (pintype "bidirectional"))
    )
    (net (code "122") (name "unconnected-(PCB1-161{slash}CAM1_DN0*-Pad161)") (class "Default")
      (node (ref "PCB1") (pin "161") (pinfunction "161/CAM1_DN0*_161") (pintype "bidirectional"))
    )
    (net (code "123") (name "unconnected-(PCB1-162{slash}NC-Pad162)") (class "Default")
      (node (ref "PCB1") (pin "162") (pinfunction "162/NC_162") (pintype "bidirectional"))
    )
    (net (code "124") (name "unconnected-(PCB1-166{slash}TVDAC-Pad166)") (class "Default")
      (node (ref "PCB1") (pin "166") (pinfunction "166/TVDAC_166") (pintype "bidirectional"))
    )
    (net (code "125") (name "unconnected-(PCB1-168{slash}USB_OTGID-Pad168)") (class "Default")
      (node (ref "PCB1") (pin "168") (pinfunction "168/USB_OTGID_168") (pintype "bidirectional"))
    )
    (net (code "126") (name "unconnected-(PCB1-171{slash}HDMI_CEC-Pad171)") (class "Default")
      (node (ref "PCB1") (pin "171") (pinfunction "171/HDMI_CEC_171") (pintype "bidirectional"))
    )
    (net (code "127") (name "unconnected-(PCB1-172{slash}VC_TRST_N-Pad172)") (class "Default")
      (node (ref "PCB1") (pin "172") (pinfunction "172/VC_TRST_N_172") (pintype "bidirectional"))
    )
    (net (code "128") (name "unconnected-(PCB1-173{slash}HDMI_SDA-Pad173)") (class "Default")
      (node (ref "PCB1") (pin "173") (pinfunction "173/HDMI_SDA_173") (pintype "bidirectional"))
    )
    (net (code "129") (name "unconnected-(PCB1-174{slash}VC_TDI-Pad174)") (class "Default")
      (node (ref "PCB1") (pin "174") (pinfunction "174/VC_TDI_174") (pintype "bidirectional"))
    )
    (net (code "130") (name "unconnected-(PCB1-175{slash}HDMI_SCL-Pad175)") (class "Default")
      (node (ref "PCB1") (pin "175") (pinfunction "175/HDMI_SCL_175") (pintype "bidirectional"))
    )
    (net (code "131") (name "unconnected-(PCB1-176{slash}VC_TMS-Pad176)") (class "Default")
      (node (ref "PCB1") (pin "176") (pinfunction "176/VC_TMS_176") (pintype "bidirectional"))
    )
    (net (code "132") (name "unconnected-(PCB1-178{slash}VC_TDO-Pad178)") (class "Default")
      (node (ref "PCB1") (pin "178") (pinfunction "178/VC_TDO_178") (pintype "bidirectional"))
    )
    (net (code "133") (name "unconnected-(PCB1-179{slash}VDD_CORE-Pad179)") (class "Default")
      (node (ref "PCB1") (pin "179") (pinfunction "179/VDD_CORE_179") (pintype "bidirectional"))
    )
    (net (code "134") (name "unconnected-(PCB1-180{slash}VC_TCK-Pad180)") (class "Default")
      (node (ref "PCB1") (pin "180") (pinfunction "180/VC_TCK_180") (pintype "bidirectional"))
    )
    (net (code "135") (name "unconnected-(PCB1-190{slash}VDAC-Pad190)") (class "Default")
      (node (ref "PCB1") (pin "190") (pinfunction "190/VDAC_190") (pintype "bidirectional"))
    )
    (net (code "136") (name "unconnected-(U1-NC-Pad5)") (class "Default")
      (node (ref "U1") (pin "5") (pinfunction "NC_5") (pintype "no_connect"))
    )
    (net (code "137") (name "unconnected-(U1-NC-Pad11)") (class "Default")
      (node (ref "U1") (pin "11") (pinfunction "NC_11") (pintype "no_connect"))
    )
  )
)
